# LoraThu.net
KiCad netlist of a schematic drawn in Altium Designer
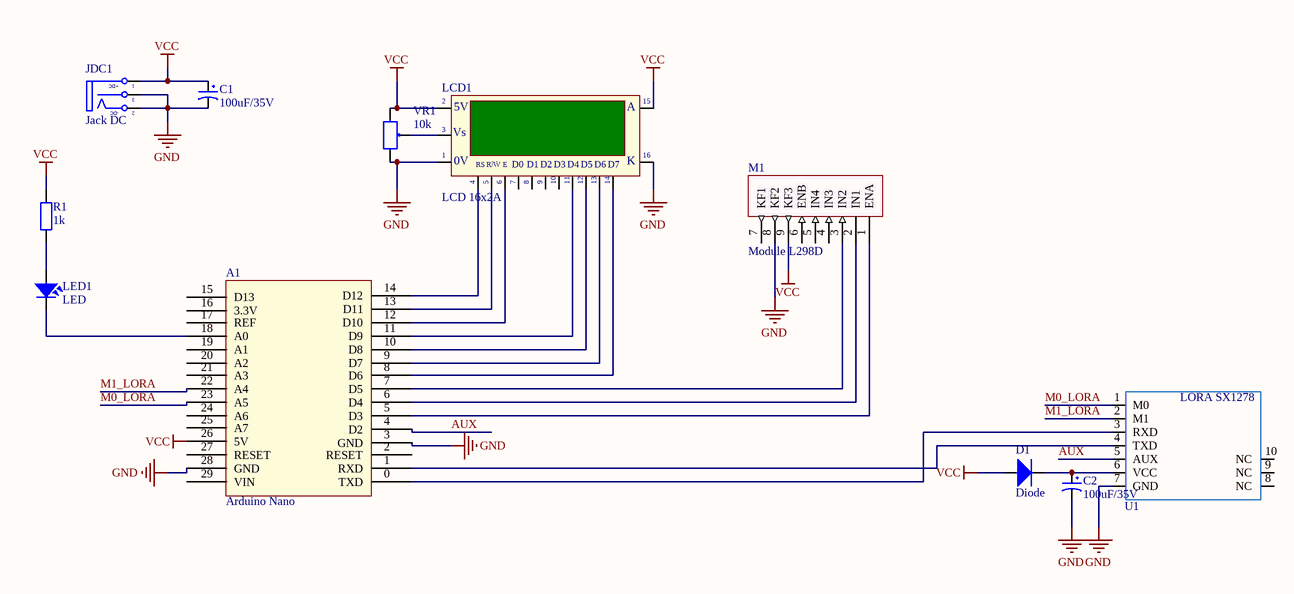
[diagram p0: LoraThu.SchDoc]

(export (version "E")
  (design (tool "Eeschema 10.0.6"))
  (components
    (comp (ref "A1")
      (value "Arduino Nano")
      (footprint "Arduino Nano")
      (libsource (lib "OBIT_TESLA") (part "Arduino Nano"))
    )
    (comp (ref "C1")
      (value "100uF/35V")
      (footprint "CP1.5/3.4")
      (description "Cap 100uF/35V - 470uF/16V")
      (libsource (lib "OBIT_TESLA") (part "CP3"))
    )
    (comp (ref "C2")
      (value "100uF/35V")
      (footprint "CP1.5/3.4")
      (description "Cap 100uF/35V - 470uF/16V")
      (libsource (lib "OBIT_TESLA") (part "CP3"))
    )
    (comp (ref "D1") (value "Diode") (footprint "DIO-SMD-106") (libsource (lib "OBIT_TESLA") (part "Diode")))
    (comp (ref "JDC1")
      (value "Jack DC")
      (footprint "CUI PJ-014D")
      (libsource (lib "OBIT_TESLA") (part "JACK_DC"))
    )
    (comp (ref "LCD1")
      (value "LCD 16x2A")
      (footprint "LCD16X2N")
      (description "LCD dipslay 16 char, 2 line")
      (libsource (lib "OBIT_TESLA") (part "LCD16x2A"))
    )
    (comp (ref "LED1") (value "LED") (footprint "LED-3") (libsource (lib "OBIT_TESLA") (part "LED")))
    (comp (ref "M1") (value "Module L298D") (footprint "L298") (libsource (lib "MCU") (part "Module L298D")))
    (comp (ref "R1")
      (value "1k")
      (footprint "RES-1/4W")
      (description "Resistor R1/4W")
      (libsource (lib "OBIT_TESLA") (part "R"))
    )
    (comp (ref "U1")
      (value "Lora SX1278 UART")
      (footprint "Lora_uart_sx1278")
      (libsource (lib "OBIT_TESLA") (part "Lora SX1278 UART"))
    )
    (comp (ref "VR1") (value "10k") (footprint "VR-S2") (libsource (lib "OBIT_TESLA") (part "Resistor Var")))
  )
  (nets
    (net (code "1") (name "/AUX") (class "Default")
      (node (ref "A1") (pin "4") (pinfunction "D2_4") (pintype "passive"))
      (node (ref "U1") (pin "5") (pinfunction "AUX_5") (pintype "passive"))
    )
    (net (code "2") (name "/M0_LORA") (class "Default")
      (node (ref "A1") (pin "23") (pinfunction "A5_23") (pintype "passive"))
      (node (ref "U1") (pin "1") (pinfunction "M0_1") (pintype "passive"))
    )
    (net (code "3") (name "/M1_LORA") (class "Default")
      (node (ref "A1") (pin "22") (pinfunction "A4_22") (pintype "passive"))
      (node (ref "U1") (pin "2") (pinfunction "M1_2") (pintype "passive"))
    )
    (net (code "4") (name "GND") (class "Default")
      (node (ref "A1") (pin "28") (pinfunction "GND_28") (pintype "passive"))
      (node (ref "A1") (pin "3") (pinfunction "GND_3") (pintype "passive"))
      (node (ref "C1") (pin "2") (pinfunction "2_2") (pintype "passive"))
      (node (ref "C2") (pin "2") (pinfunction "2_2") (pintype "passive"))
      (node (ref "JDC1") (pin "2") (pinfunction "TN_2") (pintype "passive"))
      (node (ref "JDC1") (pin "3") (pinfunction "S_3") (pintype "power_in"))
      (node (ref "LCD1") (pin "1") (pinfunction "GND_1") (pintype "passive"))
      (node (ref "LCD1") (pin "16") (pinfunction "K_16") (pintype "passive"))
      (node (ref "M1") (pin "8") (pinfunction "KF2_8") (pintype "output"))
      (node (ref "U1") (pin "7") (pinfunction "GND_7") (pintype "passive"))
      (node (ref "VR1") (pin "3") (pinfunction "3_3") (pintype "passive"))
    )
    (net (code "5") (name "Net-(A1-A0)") (class "Default")
      (node (ref "A1") (pin "18") (pinfunction "A0_18") (pintype "passive"))
      (node (ref "LED1") (pin "2") (pinfunction "2_2") (pintype "passive"))
    )
    (net (code "6") (name "Net-(A1-D3)") (class "Default")
      (node (ref "A1") (pin "5") (pinfunction "D3_5") (pintype "passive"))
      (node (ref "M1") (pin "1") (pinfunction "ENA_1") (pintype "power_in"))
    )
    (net (code "7") (name "Net-(A1-D4)") (class "Default")
      (node (ref "A1") (pin "6") (pinfunction "D4_6") (pintype "passive"))
      (node (ref "M1") (pin "2") (pinfunction "IN1_2") (pintype "power_in"))
    )
    (net (code "8") (name "Net-(A1-D5)") (class "Default")
      (node (ref "A1") (pin "7") (pinfunction "D5_7") (pintype "passive"))
      (node (ref "M1") (pin "3") (pinfunction "IN2_3") (pintype "input"))
    )
    (net (code "9") (name "Net-(A1-D6)") (class "Default")
      (node (ref "A1") (pin "8") (pinfunction "D6_8") (pintype "passive"))
      (node (ref "LCD1") (pin "14") (pinfunction "D7_14") (pintype "passive"))
    )
    (net (code "10") (name "Net-(A1-D7)") (class "Default")
      (node (ref "A1") (pin "9") (pinfunction "D7_9") (pintype "passive"))
      (node (ref "LCD1") (pin "13") (pinfunction "D6_13") (pintype "passive"))
    )
    (net (code "11") (name "Net-(A1-D8)") (class "Default")
      (node (ref "A1") (pin "10") (pinfunction "D8_10") (pintype "passive"))
      (node (ref "LCD1") (pin "12") (pinfunction "D5_12") (pintype "passive"))
    )
    (net (code "12") (name "Net-(A1-D9)") (class "Default")
      (node (ref "A1") (pin "11") (pinfunction "D9_11") (pintype "passive"))
      (node (ref "LCD1") (pin "11") (pinfunction "D4_11") (pintype "passive"))
    )
    (net (code "13") (name "Net-(A1-D10)") (class "Default")
      (node (ref "A1") (pin "12") (pinfunction "D10_12") (pintype "passive"))
      (node (ref "LCD1") (pin "6") (pinfunction "~{EN}_6") (pintype "passive"))
    )
    (net (code "14") (name "Net-(A1-D11)") (class "Default")
      (node (ref "A1") (pin "13") (pinfunction "D11_13") (pintype "passive"))
      (node (ref "LCD1") (pin "5") (pinfunction "R/~{W}_5") (pintype "passive"))
    )
    (net (code "15") (name "Net-(A1-D12)") (class "Default")
      (node (ref "A1") (pin "14") (pinfunction "D12_14") (pintype "passive"))
      (node (ref "LCD1") (pin "4") (pinfunction "RS_4") (pintype "passive"))
    )
    (net (code "16") (name "Net-(A1-RXD)") (class "Default")
      (node (ref "A1") (pin "1") (pinfunction "RXD_1") (pintype "passive"))
      (node (ref "U1") (pin "4") (pinfunction "TXD_4") (pintype "passive"))
    )
    (net (code "17") (name "Net-(A1-TXD)") (class "Default")
      (node (ref "A1") (pin "0") (pinfunction "TXD_0") (pintype "passive"))
      (node (ref "U1") (pin "3") (pinfunction "RXD_3") (pintype "passive"))
    )
    (net (code "18") (name "Net-(LCD1-VEE)") (class "Default")
      (node (ref "LCD1") (pin "3") (pinfunction "VEE_3") (pintype "passive"))
      (node (ref "VR1") (pin "2") (pinfunction "2_2") (pintype "passive"))
    )
    (net (code "19") (name "Net-(LED1-Pad1)") (class "Default")
      (node (ref "LED1") (pin "1") (pinfunction "1_1") (pintype "passive"))
      (node (ref "R1") (pin "1") (pinfunction "1_1") (pintype "passive"))
    )
    (net (code "20") (name "Net-(U1-VCC)") (class "Default")
      (node (ref "C2") (pin "1") (pinfunction "1_1") (pintype "passive"))
      (node (ref "D1") (pin "2") (pinfunction "2_2") (pintype "passive"))
      (node (ref "U1") (pin "6") (pinfunction "VCC_6") (pintype "passive"))
    )
    (net (code "21") (name "VCC") (class "Default")
      (node (ref "A1") (pin "26") (pinfunction "5V_26") (pintype "passive"))
      (node (ref "C1") (pin "1") (pinfunction "1_1") (pintype "passive"))
      (node (ref "D1") (pin "1") (pinfunction "1_1") (pintype "passive"))
      (node (ref "JDC1") (pin "1") (pinfunction "T_1") (pintype "passive"))
      (node (ref "LCD1") (pin "15") (pinfunction "A_15") (pintype "passive"))
      (node (ref "LCD1") (pin "2") (pinfunction "VDD_2") (pintype "passive"))
      (node (ref "M1") (pin "9") (pinfunction "KF3_9") (pintype "output"))
      (node (ref "R1") (pin "2") (pinfunction "2_2") (pintype "passive"))
      (node (ref "VR1") (pin "1") (pinfunction "1_1") (pintype "passive"))
    )
    (net (code "22") (name "unconnected-(A1-3.3V-Pad16)") (class "Default")
      (node (ref "A1") (pin "16") (pinfunction "3.3V_16") (pintype "passive"))
    )
    (net (code "23") (name "unconnected-(A1-A1-Pad19)") (class "Default")
      (node (ref "A1") (pin "19") (pinfunction "A1_19") (pintype "passive"))
    )
    (net (code "24") (name "unconnected-(A1-A2-Pad20)") (class "Default")
      (node (ref "A1") (pin "20") (pinfunction "A2_20") (pintype "passive"))
    )
    (net (code "25") (name "unconnected-(A1-A3-Pad21)") (class "Default")
      (node (ref "A1") (pin "21") (pinfunction "A3_21") (pintype "passive"))
    )
    (net (code "26") (name "unconnected-(A1-A6-Pad24)") (class "Default")
      (node (ref "A1") (pin "24") (pinfunction "A6_24") (pintype "passive"))
    )
    (net (code "27") (name "unconnected-(A1-A7-Pad25)") (class "Default")
      (node (ref "A1") (pin "25") (pinfunction "A7_25") (pintype "passive"))
    )
    (net (code "28") (name "unconnected-(A1-D13-Pad15)") (class "Default")
      (node (ref "A1") (pin "15") (pinfunction "D13_15") (pintype "passive"))
    )
    (net (code "29") (name "unconnected-(A1-REF-Pad17)") (class "Default")
      (node (ref "A1") (pin "17") (pinfunction "REF_17") (pintype "passive"))
    )
    (net (code "30") (name "unconnected-(A1-RESET-Pad2)") (class "Default")
      (node (ref "A1") (pin "2") (pinfunction "RESET_2") (pintype "passive"))
    )
    (net (code "31") (name "unconnected-(A1-RESET-Pad27)") (class "Default")
      (node (ref "A1") (pin "27") (pinfunction "RESET_27") (pintype "passive"))
    )
    (net (code "32") (name "unconnected-(A1-VIN-Pad29)") (class "Default")
      (node (ref "A1") (pin "29") (pinfunction "VIN_29") (pintype "passive"))
    )
    (net (code "33") (name "unconnected-(LCD1-D0-Pad7)") (class "Default")
      (node (ref "LCD1") (pin "7") (pinfunction "D0_7") (pintype "passive"))
    )
    (net (code "34") (name "unconnected-(LCD1-D1-Pad8)") (class "Default")
      (node (ref "LCD1") (pin "8") (pinfunction "D1_8") (pintype "passive"))
    )
    (net (code "35") (name "unconnected-(LCD1-D2-Pad9)") (class "Default")
      (node (ref "LCD1") (pin "9") (pinfunction "D2_9") (pintype "passive"))
    )
    (net (code "36") (name "unconnected-(LCD1-D3-Pad10)") (class "Default")
      (node (ref "LCD1") (pin "10") (pinfunction "D3_10") (pintype "passive"))
    )
    (net (code "37") (name "unconnected-(M1-ENB-Pad6)") (class "Default")
      (node (ref "M1") (pin "6") (pinfunction "ENB_6") (pintype "input"))
    )
    (net (code "38") (name "unconnected-(M1-IN3-Pad4)") (class "Default")
      (node (ref "M1") (pin "4") (pinfunction "IN3_4") (pintype "input"))
    )
    (net (code "39") (name "unconnected-(M1-IN4-Pad5)") (class "Default")
      (node (ref "M1") (pin "5") (pinfunction "IN4_5") (pintype "input"))
    )
    (net (code "40") (name "unconnected-(M1-KF1-Pad7)") (class "Default")
      (node (ref "M1") (pin "7") (pinfunction "KF1_7") (pintype "output"))
    )
    (net (code "41") (name "unconnected-(U1-NC-Pad8)") (class "Default")
      (node (ref "U1") (pin "8") (pinfunction "NC_8") (pintype "passive"))
    )
    (net (code "42") (name "unconnected-(U1-NC-Pad9)") (class "Default")
      (node (ref "U1") (pin "9") (pinfunction "NC_9") (pintype "passive"))
    )
    (net (code "43") (name "unconnected-(U1-NC-Pad10)") (class "Default")
      (node (ref "U1") (pin "10") (pinfunction "NC_10") (pintype "passive"))
    )
  )
)
